# DCTODC_Multioutput.net
KiCad netlist of a schematic drawn in Altium Designer
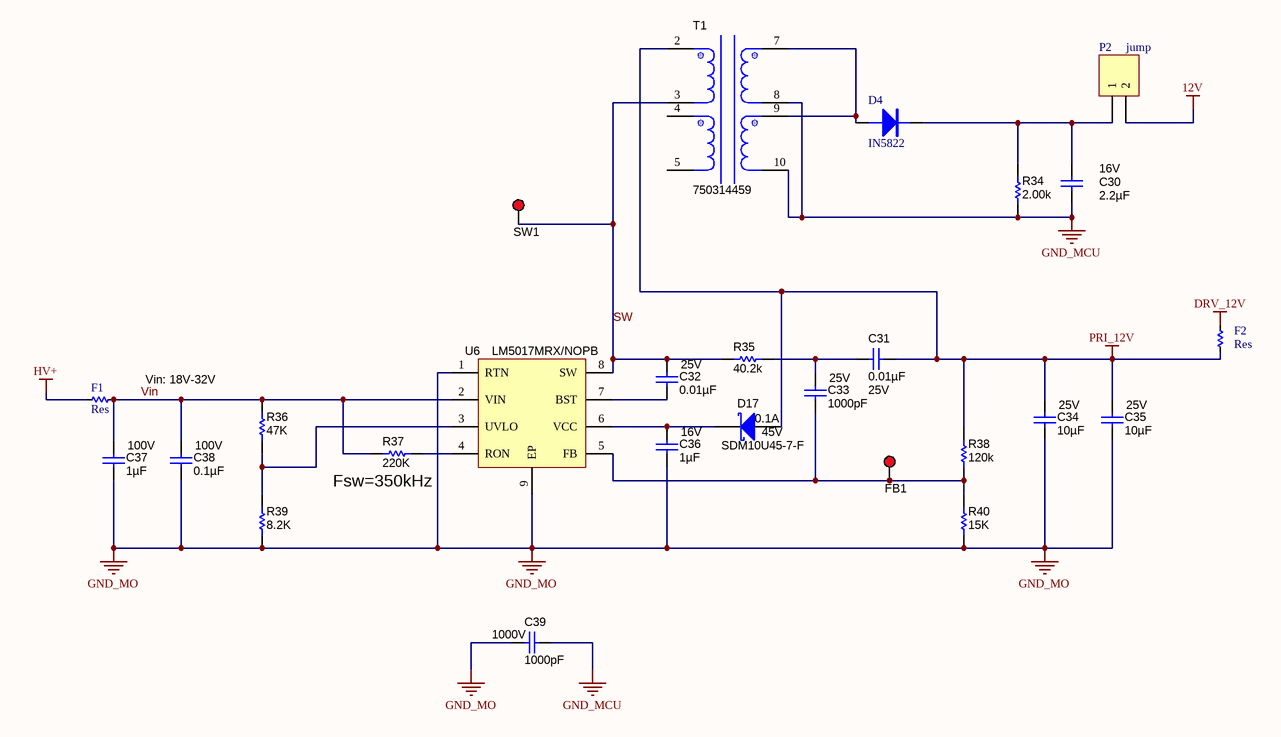
[diagram p0: DCTODC_Multioutput.SchDoc]

(export (version "E")
  (design (tool "Eeschema 10.0.6"))
  (components
    (comp (ref "C30")
      (value "C0805C225K4RACTU")
      (footprint "0805_HV")
      (description "CAP, CERM, 2.2 µF, 16 V, +/- 10%, X7R, 0805")
      (fields
        (field (name "VALUEDISPLAYED") "2.2µF")
        (field (name "MANUFACTURER") "Kemet")
        (field (name "VALUE2") "16V")
        (field (name "PUBLISHER") "Texas Instruments")
      )
      (libsource (lib "Capacitor_Ceramic") (part "C0805C225K4RACTU"))
    )
    (comp (ref "C31")
      (value "C1608C0G1E103J")
      (footprint "0805_hv")
      (description "CAP, CERM, 0.01 µF, 25 V, +/- 5%, C0G/NP0, 0603")
      (fields
        (field (name "VALUEDISPLAYED") "0.01µF")
        (field (name "MANUFACTURER") "TDK")
        (field (name "VALUE2") "25V")
        (field (name "PUBLISHER") "Texas Instruments")
      )
      (libsource (lib "Capacitor_Ceramic") (part "C1608C0G1E103J"))
    )
    (comp (ref "C32")
      (value "C1608C0G1E103J")
      (footprint "0805_HV")
      (description "CAP, CERM, 0.01 µF, 25 V, +/- 5%, C0G/NP0, 0603")
      (fields
        (field (name "VALUEDISPLAYED") "0.01µF")
        (field (name "MANUFACTURER") "TDK")
        (field (name "VALUE2") "25V")
        (field (name "PUBLISHER") "Texas Instruments")
      )
      (libsource (lib "Capacitor_Ceramic") (part "C1608C0G1E103J"))
    )
    (comp (ref "C33")
      (value "GRM1885C1E102JA01D")
      (footprint "0805_hv")
      (description "CAP, CERM, 1000 pF, 25 V, +/- 5%, C0G/NP0, 0603")
      (fields
        (field (name "VALUEDISPLAYED") "1000pF")
        (field (name "MANUFACTURER") "MuRata")
        (field (name "VALUE2") "25V")
        (field (name "PUBLISHER") "Texas Instruments")
      )
      (libsource (lib "Capacitor_Ceramic") (part "GRM1885C1E102JA01D"))
    )
    (comp (ref "C34")
      (value "C3225X7R1E106M")
      (footprint "1210")
      (description "CAP, CERM, 10 µF, 25 V, +/- 20%, X7R, 1210")
      (fields
        (field (name "VALUEDISPLAYED") "10µF")
        (field (name "MANUFACTURER") "TDK")
        (field (name "VALUE2") "25V")
        (field (name "PUBLISHER") "Texas Instruments")
      )
      (libsource (lib "Capacitor_Ceramic") (part "C3225X7R1E106M"))
    )
    (comp (ref "C35")
      (value "C3225X7R1E106M")
      (footprint "1210")
      (description "CAP, CERM, 10 µF, 25 V, +/- 20%, X7R, 1210")
      (fields
        (field (name "VALUEDISPLAYED") "10µF")
        (field (name "MANUFACTURER") "TDK")
        (field (name "VALUE2") "25V")
        (field (name "PUBLISHER") "Texas Instruments")
      )
      (libsource (lib "Capacitor_Ceramic") (part "C3225X7R1E106M"))
    )
    (comp (ref "C36")
      (value "C1608X5R1C105K")
      (footprint "0805_HV")
      (description "CAP, CERM, 1 µF, 16 V, +/- 10%, X5R, 0603")
      (fields
        (field (name "VALUEDISPLAYED") "1µF")
        (field (name "MANUFACTURER") "TDK")
        (field (name "VALUE2") "16V")
        (field (name "PUBLISHER") "Texas Instruments")
      )
      (libsource (lib "Capacitor_Ceramic") (part "C1608X5R1C105K"))
    )
    (comp (ref "C37")
      (value "C3225X7R2A105K200AA")
      (footprint "1210")
      (description "CAP, CERM, 1 µF, 100 V, +/- 10%, X7R, 1210")
      (fields
        (field (name "VALUEDISPLAYED") "1µF")
        (field (name "MANUFACTURER") "TDK")
        (field (name "VALUE2") "100V")
        (field (name "PUBLISHER") "Texas Instruments")
      )
      (libsource (lib "Capacitor_Ceramic") (part "C3225X7R2A105K200AA"))
    )
    (comp (ref "C38")
      (value "C2012X7R2A104K")
      (footprint "0805_HV")
      (description "CAP, CERM, 0.1 µF, 100 V, +/- 10%, X7R, 0805")
      (fields
        (field (name "VALUEDISPLAYED") "0.1µF")
        (field (name "MANUFACTURER") "TDK")
        (field (name "VALUE2") "100V")
        (field (name "PUBLISHER") "Texas Instruments")
      )
      (libsource (lib "Capacitor_Ceramic") (part "C2012X7R2A104K"))
    )
    (comp (ref "C39")
      (value "VJ1210A102JXGAT5Z")
      (footprint "1210")
      (description "CAP, CERM, 1000 pF, 1000 V, +/- 5%, C0G/NP0, 1210")
      (fields
        (field (name "VALUEDISPLAYED") "1000pF")
        (field (name "MANUFACTURER") "Vishay-Vitramon")
        (field (name "VALUE2") "1000V")
        (field (name "PUBLISHER") "Texas Instruments")
      )
      (libsource (lib "Capacitor_Ceramic") (part "VJ1210A102JXGAT5Z"))
    )
    (comp (ref "D4")
      (value "IN5822")
      (footprint "SOD123")
      (description "Diode S4 SOD123 ( 1N5819 SOD123)")
      (libsource (lib "MH_DA_THU_VIEN_16122016") (part "Diode S4 SOD123 ( 1N5819 SOD123)_MH"))
    )
    (comp (ref "D17")
      (value "SDM10U45-7-F")
      (footprint "SOD-123")
      (description "Diode, Schottky, 45 V, 0.1 A, SOD-523")
      (fields
        (field (name "MANUFACTURER") "Diodes Inc.")
        (field (name "VALUE1") "0.1A")
        (field (name "VR_V") "45V")
        (field (name "PUBLISHER") "Texas Instruments")
      )
      (libsource (lib "Diode") (part "SDM10U45-7-F"))
    )
    (comp (ref "F1")
      (value "Res")
      (footprint "1206")
      (description "Resistor")
      (fields
        (field (name "MANUFACTURER") "Generic Components")
        (field (name "PUBLISHER") "Altium Hobart Technology Centre")
      )
      (libsource (lib "LIBRARY") (part "Res-SMD"))
    )
    (comp (ref "F2")
      (value "Res")
      (footprint "1206")
      (description "Resistor")
      (fields
        (field (name "MANUFACTURER") "Generic Components")
        (field (name "PUBLISHER") "Altium Hobart Technology Centre")
      )
      (libsource (lib "LIBRARY") (part "Res-SMD"))
    )
    (comp (ref "FB1")
      (value "5000")
      (footprint "Keystone5000")
      (description "Test Point, Miniature, Red, TH")
      (fields (field (name "MANUFACTURER") "Keystone") (field (name "PUBLISHER") "Texas Instruments"))
      (libsource (lib "Connectors") (part "5000"))
    )
    (comp (ref "P2")
      (value "jump")
      (footprint "HDR1X2")
      (description "Header, 2-Pin")
      (fields (field (name "PUBLISHER") "Altium Limited"))
      (libsource (lib "Miscellaneous Connectors") (part "Header 2"))
    )
    (comp (ref "R34")
      (value "CRCW06032K00FKEA")
      (footprint "0805_hv")
      (description "RES, 2.00 k, 1%, 0.1 W, 0603")
      (fields
        (field (name "VALUEDISPLAYED") "2.00k")
        (field (name "MANUFACTURER") "Vishay-Dale")
        (field (name "PUBLISHER") "Texas Instruments")
      )
      (libsource (lib "Resistor_0603") (part "CRCW06032K00FKEA"))
    )
    (comp (ref "R35")
      (value "RC0603FR-0740K2L")
      (footprint "0805_HV")
      (description "RES, 40.2 k, 1%, 0.1 W, 0603")
      (fields
        (field (name "VALUEDISPLAYED") "40.2k")
        (field (name "MANUFACTURER") "Yageo America")
        (field (name "PUBLISHER") "Texas Instruments")
      )
      (libsource (lib "Resistor_0603") (part "RC0603FR-0740K2L"))
    )
    (comp (ref "R36")
      (value "CRCW0603100KFKEA")
      (footprint "0805_HV")
      (description "RES, 100 k, 1%, 0.1 W, 0603")
      (fields
        (field (name "VALUEDISPLAYED") "47K")
        (field (name "MANUFACTURER") "Vishay-Dale")
        (field (name "PUBLISHER") "Texas Instruments")
      )
      (libsource (lib "Resistor_0603") (part "CRCW0603100KFKEA"))
    )
    (comp (ref "R37")
      (value "1879339-3")
      (footprint "0805_HV")
      (description "RES, 301 k, 1%, 0.063 W, 0603")
      (fields
        (field (name "MANUFACTURER") "TE Connectivity")
        (field (name "VALUEDISPLAYED") "220K")
        (field (name "PUBLISHER") "Texas Instruments")
      )
      (libsource (lib "Resistor_0603") (part "1879339-3"))
    )
    (comp (ref "R38")
      (value "RT0603DRE07140KL")
      (footprint "0805_hv")
      (description "RES, 140 k, 0.5%, 0.1 W, 0603")
      (fields
        (field (name "VALUEDISPLAYED") "120k")
        (field (name "MANUFACTURER") "Yageo America")
        (field (name "PUBLISHER") "Texas Instruments")
      )
      (libsource (lib "Resistor_0603") (part "RT0603DRE07140KL"))
    )
    (comp (ref "R39")
      (value "CRCW06038K87FKEA")
      (footprint "0805_HV")
      (description "RES, 8.87 k, 1%, 0.1 W, 0603")
      (fields
        (field (name "VALUEDISPLAYED") "8.2K")
        (field (name "MANUFACTURER") "Vishay-Dale")
        (field (name "PUBLISHER") "Texas Instruments")
      )
      (libsource (lib "Resistor_0603") (part "CRCW06038K87FKEA"))
    )
    (comp (ref "R40")
      (value "CRCW060320K0FKEA")
      (footprint "0805_hv")
      (description "RES, 20.0 k, 1%, 0.1 W, 0603")
      (fields
        (field (name "VALUEDISPLAYED") "15K")
        (field (name "MANUFACTURER") "Vishay-Dale")
        (field (name "PUBLISHER") "Texas Instruments")
      )
      (libsource (lib "Resistor_0603") (part "CRCW060320K0FKEA"))
    )
    (comp (ref "SW1")
      (value "5000")
      (footprint "Keystone5000")
      (description "Test Point, Miniature, Red, TH")
      (fields (field (name "MANUFACTURER") "Keystone") (field (name "PUBLISHER") "Texas Instruments"))
      (libsource (lib "Connectors") (part "5000"))
    )
    (comp (ref "T1")
      (value "750314459")
      (footprint "POE13P")
      (description "XFMR, SMT 45uH, 750314459")
      (fields (field (name "MANUFACTURER") "Wurth"))
      (libsource (lib "Schlib1") (part "POE13"))
    )
    (comp (ref "U6")
      (value "LM5017MRX/NOPB")
      (footprint "MRA08A_N")
      (description "100V Constant On-Time PFET Buck Switching Controller, 8-pin PSOP, Pb-Free")
      (fields
        (field (name "MANUFACTURER") "National Semiconductor")
        (field (name "PUBLISHER") "Altium Limited")
      )
      (libsource (lib "My Library") (part "LM5017MRX/NOPB"))
    )
  )
  (nets
    (net (code "1") (name "/SW") (class "Default")
      (node (ref "C32") (pin "1") (pinfunction "1_1") (pintype "passive"))
      (node (ref "R35") (pin "1") (pinfunction "1_1") (pintype "passive"))
      (node (ref "SW1") (pin "1") (pintype "passive"))
      (node (ref "T1") (pin "3") (pintype "passive"))
      (node (ref "U6") (pin "8") (pinfunction "SW_8") (pintype "passive"))
    )
    (net (code "2") (name "/Vin") (class "Default")
      (node (ref "C37") (pin "1") (pinfunction "1_1") (pintype "passive"))
      (node (ref "C38") (pin "1") (pinfunction "1_1") (pintype "passive"))
      (node (ref "F1") (pin "1") (pinfunction "1_1") (pintype "passive"))
      (node (ref "R36") (pin "2") (pinfunction "2_2") (pintype "passive"))
      (node (ref "R37") (pin "1") (pinfunction "1_1") (pintype "passive"))
      (node (ref "U6") (pin "2") (pinfunction "VIN_2") (pintype "passive"))
    )
    (net (code "3") (name "12V") (class "Default")
      (node (ref "P2") (pin "2") (pinfunction "2_2") (pintype "passive"))
    )
    (net (code "4") (name "DRV_12V") (class "Default")
      (node (ref "F2") (pin "2") (pinfunction "2_2") (pintype "passive"))
    )
    (net (code "5") (name "GND_MCU") (class "Default")
      (node (ref "C30") (pin "2") (pinfunction "2_2") (pintype "passive"))
      (node (ref "C39") (pin "1") (pinfunction "1_1") (pintype "passive"))
      (node (ref "R34") (pin "1") (pinfunction "1_1") (pintype "passive"))
      (node (ref "T1") (pin "10") (pintype "passive"))
      (node (ref "T1") (pin "8") (pintype "passive"))
    )
    (net (code "6") (name "GND_MO") (class "Default")
      (node (ref "C34") (pin "2") (pinfunction "2_2") (pintype "passive"))
      (node (ref "C35") (pin "2") (pinfunction "2_2") (pintype "passive"))
      (node (ref "C36") (pin "2") (pinfunction "2_2") (pintype "passive"))
      (node (ref "C37") (pin "2") (pinfunction "2_2") (pintype "passive"))
      (node (ref "C38") (pin "2") (pinfunction "2_2") (pintype "passive"))
      (node (ref "C39") (pin "2") (pinfunction "2_2") (pintype "passive"))
      (node (ref "R39") (pin "1") (pinfunction "1_1") (pintype "passive"))
      (node (ref "R40") (pin "1") (pinfunction "1_1") (pintype "passive"))
      (node (ref "U6") (pin "1") (pinfunction "RTN_1") (pintype "passive"))
      (node (ref "U6") (pin "9") (pinfunction "EP_9") (pintype "passive"))
    )
    (net (code "7") (name "HV+") (class "Default")
      (node (ref "F1") (pin "2") (pinfunction "2_2") (pintype "passive"))
    )
    (net (code "8") (name "Net-(C30-Pad1)") (class "Default")
      (node (ref "C30") (pin "1") (pinfunction "1_1") (pintype "passive"))
      (node (ref "D4") (pin "2") (pinfunction "2_2") (pintype "passive"))
      (node (ref "P2") (pin "1") (pinfunction "1_1") (pintype "passive"))
      (node (ref "R34") (pin "2") (pinfunction "2_2") (pintype "passive"))
    )
    (net (code "9") (name "Net-(C31-Pad1)") (class "Default")
      (node (ref "C31") (pin "1") (pinfunction "1_1") (pintype "passive"))
      (node (ref "C33") (pin "1") (pinfunction "1_1") (pintype "passive"))
      (node (ref "R35") (pin "2") (pinfunction "2_2") (pintype "passive"))
    )
    (net (code "10") (name "Net-(D4-Pad1)") (class "Default")
      (node (ref "D4") (pin "1") (pinfunction "1_1") (pintype "passive"))
      (node (ref "T1") (pin "7") (pintype "passive"))
      (node (ref "T1") (pin "9") (pintype "passive"))
    )
    (net (code "11") (name "Net-(D17-K)") (class "Default")
      (node (ref "C36") (pin "1") (pinfunction "1_1") (pintype "passive"))
      (node (ref "D17") (pin "1") (pinfunction "K_1") (pintype "passive"))
      (node (ref "U6") (pin "6") (pinfunction "VCC_6") (pintype "passive"))
    )
    (net (code "12") (name "Net-(U6-BST)") (class "Default")
      (node (ref "C32") (pin "2") (pinfunction "2_2") (pintype "passive"))
      (node (ref "U6") (pin "7") (pinfunction "BST_7") (pintype "power_in"))
    )
    (net (code "13") (name "Net-(U6-FB)") (class "Default")
      (node (ref "C33") (pin "2") (pinfunction "2_2") (pintype "passive"))
      (node (ref "FB1") (pin "1") (pintype "passive"))
      (node (ref "R38") (pin "1") (pinfunction "1_1") (pintype "passive"))
      (node (ref "R40") (pin "2") (pinfunction "2_2") (pintype "passive"))
      (node (ref "U6") (pin "5") (pinfunction "FB_5") (pintype "passive"))
    )
    (net (code "14") (name "Net-(U6-RON)") (class "Default")
      (node (ref "R37") (pin "2") (pinfunction "2_2") (pintype "passive"))
      (node (ref "U6") (pin "4") (pinfunction "RON_4") (pintype "power_in"))
    )
    (net (code "15") (name "Net-(U6-UVLO)") (class "Default")
      (node (ref "R36") (pin "1") (pinfunction "1_1") (pintype "passive"))
      (node (ref "R39") (pin "2") (pinfunction "2_2") (pintype "passive"))
      (node (ref "U6") (pin "3") (pinfunction "UVLO_3") (pintype "passive"))
    )
    (net (code "16") (name "PRI_12V") (class "Default")
      (node (ref "C31") (pin "2") (pinfunction "2_2") (pintype "passive"))
      (node (ref "C34") (pin "1") (pinfunction "1_1") (pintype "passive"))
      (node (ref "C35") (pin "1") (pinfunction "1_1") (pintype "passive"))
      (node (ref "D17") (pin "2") (pinfunction "A_2") (pintype "passive"))
      (node (ref "F2") (pin "1") (pinfunction "1_1") (pintype "passive"))
      (node (ref "R38") (pin "2") (pinfunction "2_2") (pintype "passive"))
      (node (ref "T1") (pin "2") (pintype "passive"))
    )
    (net (code "17") (name "unconnected-(T1-Pad4)") (class "Default")
      (node (ref "T1") (pin "4") (pintype "passive"))
    )
    (net (code "18") (name "unconnected-(T1-Pad5)") (class "Default")
      (node (ref "T1") (pin "5") (pintype "passive"))
    )
  )
)
